# Main.net
KiCad netlist of a schematic drawn in Altium Designer
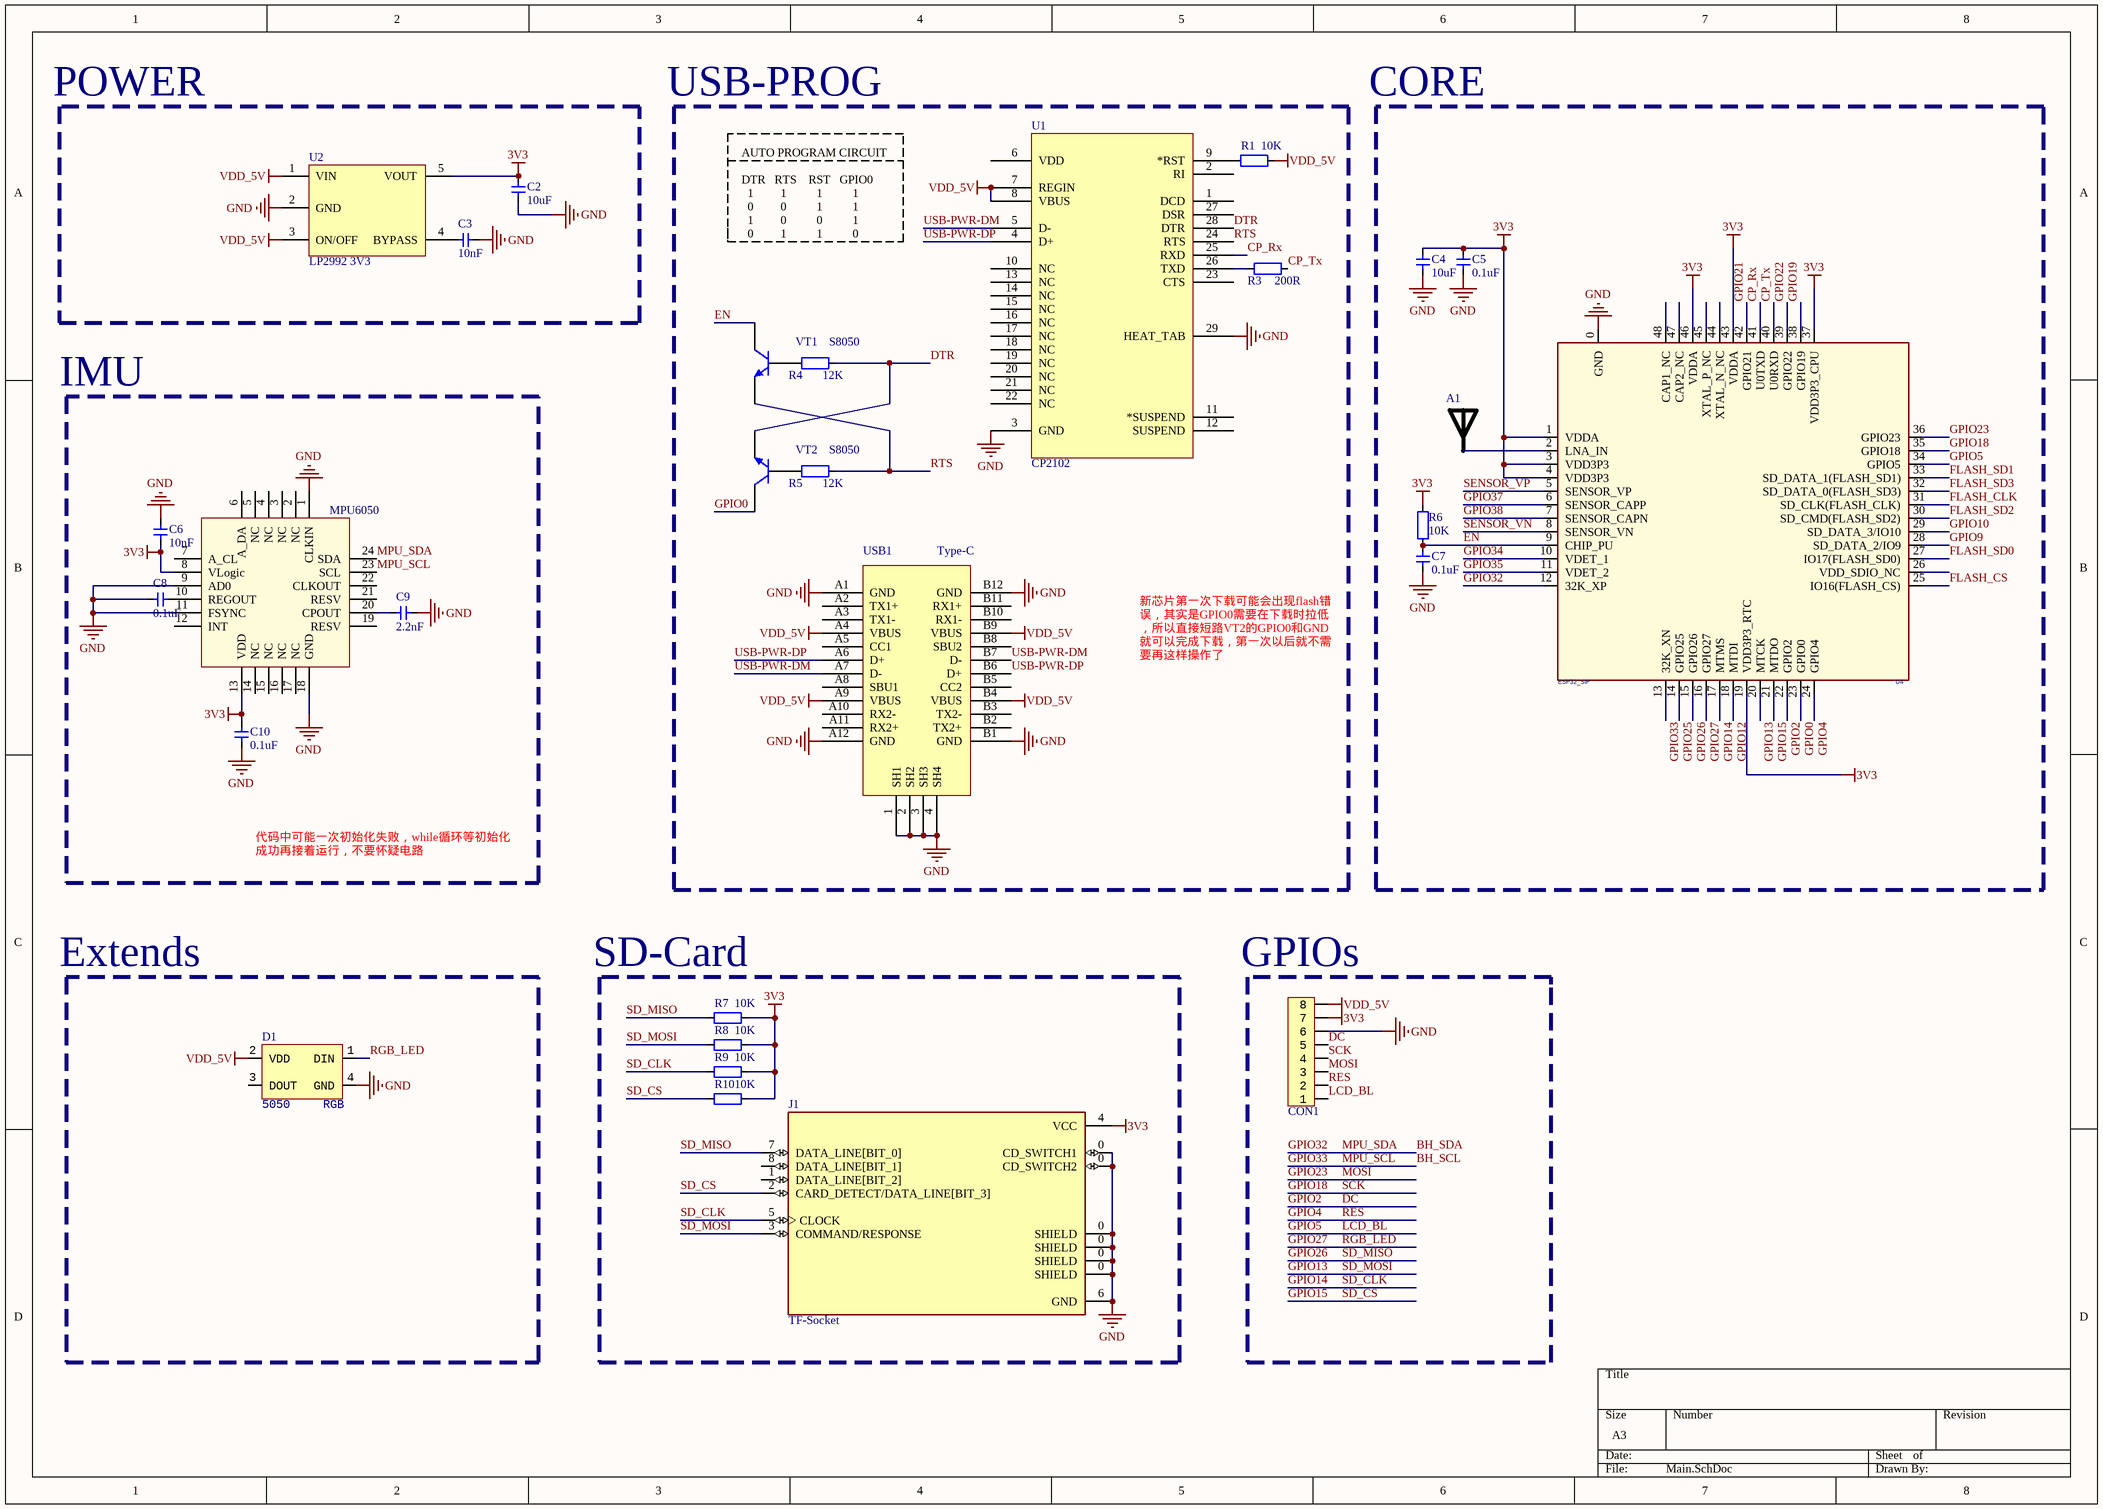
[diagram p0: Main.SchDoc]

(export (version "E")
  (design (tool "Eeschema 10.0.6"))
  (components
    (comp (ref "A1")
      (value "RAINSUN")
      (footprint "ANT-Rainsun-AN5120")
      (libsource (lib "MyPcbLib") (part "ANT-Rainsun-AP5120"))
    )
    (comp (ref "C2")
      (value "10uF")
      (footprint "CAP_0402")
      (description "Capacitor")
      (libsource (lib "MyPcbLib") (part "电容-0402"))
    )
    (comp (ref "C3")
      (value "10nF")
      (footprint "CAP_0402")
      (description "Capacitor")
      (libsource (lib "MyPcbLib") (part "电容-0402"))
    )
    (comp (ref "C4")
      (value "10uF")
      (footprint "CAP_0402")
      (description "Capacitor")
      (libsource (lib "MyPcbLib") (part "电容-0402"))
    )
    (comp (ref "C5")
      (value "0.1uF")
      (footprint "CAP_0402")
      (description "Capacitor")
      (libsource (lib "MyPcbLib") (part "电容-0402"))
    )
    (comp (ref "C6")
      (value "10nF")
      (footprint "CAP_0402")
      (description "Capacitor")
      (libsource (lib "MyPcbLib") (part "电容-0402"))
    )
    (comp (ref "C7")
      (value "0.1uF")
      (footprint "CAP_0402")
      (description "Capacitor")
      (libsource (lib "MyPcbLib") (part "电容-0402"))
    )
    (comp (ref "C8")
      (value "0.1uF")
      (footprint "CAP_0402")
      (description "Capacitor")
      (libsource (lib "MyPcbLib") (part "电容-0402"))
    )
    (comp (ref "C9")
      (value "2.2nF")
      (footprint "CAP_0402")
      (description "Capacitor")
      (libsource (lib "MyPcbLib") (part "电容-0402"))
    )
    (comp (ref "C10")
      (value "0.1uF")
      (footprint "CAP_0402")
      (description "Capacitor")
      (libsource (lib "MyPcbLib") (part "电容-0402"))
    )
    (comp (ref "CON1")
      (value "FFC_0.5_8")
      (footprint "FFC_0.5_8")
      (description "FFC")
      (libsource (lib "KitSprout") (part "FFC_0.5_8"))
    )
    (comp (ref "D1")
      (value "RGB")
      (footprint "LED_WS2812_CE")
      (description "LED")
      (fields (field (name "TYPE") "5050"))
      (libsource (lib "KitSprout") (part "LED_5050_WS2812B"))
    )
    (comp (ref "J1")
      (value "TF-Socket")
      (footprint "TF_F")
      (description "10 _8 + 2_ Position Card Connector Secure Digital - microSDâ„¢ Surface Mount, Right Angle Gold")
      (fields (field (name "MP") "1140084168") (field (name "MF") "Amphenol Commercial Products"))
      (libsource (lib "MyPcbLib") (part "TF-Socket"))
    )
    (comp (ref "R1")
      (value "10K")
      (footprint "RES_0402")
      (description "Resistor")
      (libsource (lib "MyPcbLib") (part "电阻-0402"))
    )
    (comp (ref "R3")
      (value "200R")
      (footprint "RES_0402")
      (description "Resistor")
      (libsource (lib "MyPcbLib") (part "电阻-0402"))
    )
    (comp (ref "R4")
      (value "12K")
      (footprint "RES_0402")
      (description "Resistor")
      (libsource (lib "MyPcbLib") (part "电阻-0402"))
    )
    (comp (ref "R5")
      (value "12K")
      (footprint "RES_0402")
      (description "Resistor")
      (libsource (lib "MyPcbLib") (part "电阻-0402"))
    )
    (comp (ref "R6")
      (value "10K")
      (footprint "RES_0402")
      (description "Resistor")
      (libsource (lib "") (part "电阻-0402_1"))
    )
    (comp (ref "R7")
      (value "10K")
      (footprint "RES_0402")
      (description "Resistor")
      (libsource (lib "MyPcbLib") (part "电阻-0402"))
    )
    (comp (ref "R8")
      (value "10K")
      (footprint "RES_0402")
      (description "Resistor")
      (libsource (lib "MyPcbLib") (part "电阻-0402"))
    )
    (comp (ref "R9")
      (value "10K")
      (footprint "RES_0402")
      (description "Resistor")
      (libsource (lib "MyPcbLib") (part "电阻-0402"))
    )
    (comp (ref "R10")
      (value "10K")
      (footprint "RES_0402")
      (description "Resistor")
      (libsource (lib "MyPcbLib") (part "电阻-0402"))
    )
    (comp (ref "U1")
      (value "CP2102")
      (footprint "QFN-28")
      (description "USB转TTL")
      (libsource (lib "mLib") (part "CP2102"))
    )
    (comp (ref "U2")
      (value "LP2992 3V3")
      (footprint "SOT23-5")
      (description "LDO")
      (libsource (lib "MyPcbLib") (part "LP2992"))
    )
    (comp (ref "U3")
      (value "MPU6050")
      (footprint "QFN-24")
      (description "六轴传感器")
      (libsource (lib "mLib") (part "MPU6050"))
    )
    (comp (ref "U4")
      (value "ESP32_SIP")
      (footprint "QFN-48_7X7")
      (libsource (lib "MyPcbLib") (part "ESP32-PICO"))
    )
    (comp (ref "USB1")
      (value "Type-C")
      (footprint "Type-C-TOP")
      (libsource (lib "MyPcbLib") (part "USB-Type-C-TOP"))
    )
    (comp (ref "VT1")
      (value "S8050")
      (footprint "SMT_TRIODE_NPN")
      (description "Surface mount NPN transistor, package SOT-23")
      (libsource (lib "MyPcbLib") (part "SMT_TRIODE_NPN"))
    )
    (comp (ref "VT2")
      (value "S8050")
      (footprint "SMT_TRIODE_NPN")
      (description "Surface mount NPN transistor, package SOT-23")
      (libsource (lib "MyPcbLib") (part "SMT_TRIODE_NPN"))
    )
  )
  (nets
    (net (code "1") (name "/BH_SCL") (class "Default")
      (node (ref "U3") (pin "23") (pinfunction "SCL_23") (pintype "passive"))
      (node (ref "U4") (pin "13") (pinfunction "32K_XN_13") (pintype "passive"))
    )
    (net (code "2") (name "/BH_SDA") (class "Default")
      (node (ref "U3") (pin "24") (pinfunction "SDA_24") (pintype "passive"))
      (node (ref "U4") (pin "12") (pinfunction "32K_XP_12") (pintype "passive"))
    )
    (net (code "3") (name "/CP_Rx") (class "Default")
      (node (ref "U1") (pin "25") (pinfunction "RXD_25") (pintype "passive"))
      (node (ref "U4") (pin "41") (pinfunction "U0TXD_41") (pintype "power_in"))
    )
    (net (code "4") (name "/CP_Tx") (class "Default")
      (node (ref "R3") (pin "1") (pinfunction "1_1") (pintype "passive"))
      (node (ref "U4") (pin "40") (pinfunction "U0RXD_40") (pintype "power_in"))
    )
    (net (code "5") (name "/DC") (class "Default")
      (node (ref "CON1") (pin "5") (pinfunction "5_5") (pintype "passive"))
      (node (ref "U4") (pin "22") (pinfunction "GPIO2_22") (pintype "passive"))
    )
    (net (code "6") (name "/DTR") (class "Default")
      (node (ref "R4") (pin "1") (pinfunction "1_1") (pintype "passive"))
      (node (ref "U1") (pin "28") (pinfunction "DTR_28") (pintype "passive"))
      (node (ref "VT2") (pin "2") (pinfunction "E_2") (pintype "passive"))
    )
    (net (code "7") (name "/EN") (class "Default")
      (node (ref "C7") (pin "1") (pinfunction "1_1") (pintype "passive"))
      (node (ref "R6") (pin "2") (pinfunction "2_2") (pintype "passive"))
      (node (ref "U4") (pin "9") (pinfunction "CHIP_PU_9") (pintype "passive"))
      (node (ref "VT1") (pin "3") (pinfunction "C_3") (pintype "passive"))
    )
    (net (code "8") (name "/FLASH_CLK") (class "Default")
      (node (ref "U4") (pin "31") (pinfunction "SD_CLK(FLASH_CLK)_31") (pintype "passive"))
    )
    (net (code "9") (name "/FLASH_CS") (class "Default")
      (node (ref "U4") (pin "25") (pinfunction "IO16(FLASH_CS)_25") (pintype "passive"))
    )
    (net (code "10") (name "/FLASH_SD0") (class "Default")
      (node (ref "U4") (pin "27") (pinfunction "IO17(FLASH_SD0)_27") (pintype "passive"))
    )
    (net (code "11") (name "/FLASH_SD1") (class "Default")
      (node (ref "U4") (pin "33") (pinfunction "SD_DATA_1(FLASH_SD1)_33") (pintype "passive"))
    )
    (net (code "12") (name "/FLASH_SD2") (class "Default")
      (node (ref "U4") (pin "30") (pinfunction "SD_CMD(FLASH_SD2)_30") (pintype "passive"))
    )
    (net (code "13") (name "/FLASH_SD3") (class "Default")
      (node (ref "U4") (pin "32") (pinfunction "SD_DATA_0(FLASH_SD3)_32") (pintype "passive"))
    )
    (net (code "14") (name "/GPIO0") (class "Default")
      (node (ref "U4") (pin "23") (pinfunction "GPIO0_23") (pintype "passive"))
      (node (ref "VT2") (pin "3") (pinfunction "C_3") (pintype "passive"))
    )
    (net (code "15") (name "/GPIO4") (class "Default")
      (node (ref "CON1") (pin "2") (pinfunction "2_2") (pintype "passive"))
      (node (ref "U4") (pin "24") (pinfunction "GPIO4_24") (pintype "passive"))
    )
    (net (code "16") (name "/GPIO5") (class "Default")
      (node (ref "CON1") (pin "1") (pinfunction "1_1") (pintype "passive"))
      (node (ref "U4") (pin "34") (pinfunction "GPIO5_34") (pintype "passive"))
    )
    (net (code "17") (name "/GPIO9") (class "Default")
      (node (ref "U4") (pin "28") (pinfunction "SD_DATA_2/IO9_28") (pintype "passive"))
    )
    (net (code "18") (name "/GPIO10") (class "Default")
      (node (ref "U4") (pin "29") (pinfunction "SD_DATA_3/IO10_29") (pintype "passive"))
    )
    (net (code "19") (name "/GPIO12") (class "Default")
      (node (ref "U4") (pin "18") (pinfunction "MTDI_18") (pintype "passive"))
    )
    (net (code "20") (name "/GPIO13") (class "Default")
      (node (ref "J1") (pin "3") (pinfunction "COMMAND/RESPONSE_3") (pintype "bidirectional"))
      (node (ref "R8") (pin "2") (pinfunction "2_2") (pintype "passive"))
      (node (ref "U4") (pin "20") (pinfunction "MTCK_20") (pintype "passive"))
    )
    (net (code "21") (name "/GPIO14") (class "Default")
      (node (ref "J1") (pin "5") (pinfunction "CLOCK_5") (pintype "bidirectional"))
      (node (ref "R9") (pin "2") (pinfunction "2_2") (pintype "passive"))
      (node (ref "U4") (pin "17") (pinfunction "MTMS_17") (pintype "passive"))
    )
    (net (code "22") (name "/GPIO15") (class "Default")
      (node (ref "J1") (pin "2") (pinfunction "CARD_DETECT/DATA_LINE[BIT_3]_2") (pintype "bidirectional"))
      (node (ref "R10") (pin "2") (pinfunction "2_2") (pintype "passive"))
      (node (ref "U4") (pin "21") (pinfunction "MTDO_21") (pintype "passive"))
    )
    (net (code "23") (name "/GPIO18") (class "Default")
      (node (ref "CON1") (pin "4") (pinfunction "4_4") (pintype "passive"))
      (node (ref "U4") (pin "35") (pinfunction "GPIO18_35") (pintype "passive"))
    )
    (net (code "24") (name "/GPIO19") (class "Default")
      (node (ref "U4") (pin "38") (pinfunction "GPIO19_38") (pintype "passive"))
    )
    (net (code "25") (name "/GPIO21") (class "Default")
      (node (ref "U4") (pin "42") (pinfunction "GPIO21_42") (pintype "passive"))
    )
    (net (code "26") (name "/GPIO22") (class "Default")
      (node (ref "U4") (pin "39") (pinfunction "GPIO22_39") (pintype "passive"))
    )
    (net (code "27") (name "/GPIO23") (class "Default")
      (node (ref "CON1") (pin "3") (pinfunction "3_3") (pintype "passive"))
      (node (ref "U4") (pin "36") (pinfunction "GPIO23_36") (pintype "passive"))
    )
    (net (code "28") (name "/GPIO25") (class "Default")
      (node (ref "U4") (pin "14") (pinfunction "GPIO25_14") (pintype "passive"))
    )
    (net (code "29") (name "/GPIO26") (class "Default")
      (node (ref "J1") (pin "7") (pinfunction "DATA_LINE[BIT_0]_7") (pintype "bidirectional"))
      (node (ref "R7") (pin "2") (pinfunction "2_2") (pintype "passive"))
      (node (ref "U4") (pin "15") (pinfunction "GPIO26_15") (pintype "passive"))
    )
    (net (code "30") (name "/GPIO27") (class "Default")
      (node (ref "D1") (pin "1") (pinfunction "DIN_1") (pintype "passive"))
      (node (ref "U4") (pin "16") (pinfunction "GPIO27_16") (pintype "passive"))
    )
    (net (code "31") (name "/GPIO34") (class "Default")
      (node (ref "U4") (pin "10") (pinfunction "VDET_1_10") (pintype "passive"))
    )
    (net (code "32") (name "/GPIO35") (class "Default")
      (node (ref "U4") (pin "11") (pinfunction "VDET_2_11") (pintype "passive"))
    )
    (net (code "33") (name "/GPIO37") (class "Default")
      (node (ref "U4") (pin "6") (pinfunction "SENSOR_CAPP_6") (pintype "passive"))
    )
    (net (code "34") (name "/GPIO38") (class "Default")
      (node (ref "U4") (pin "7") (pinfunction "SENSOR_CAPN_7") (pintype "passive"))
    )
    (net (code "35") (name "/RTS") (class "Default")
      (node (ref "R5") (pin "1") (pinfunction "1_1") (pintype "passive"))
      (node (ref "U1") (pin "24") (pinfunction "RTS_24") (pintype "passive"))
      (node (ref "VT1") (pin "2") (pinfunction "E_2") (pintype "passive"))
    )
    (net (code "36") (name "/SENSOR_VN") (class "Default")
      (node (ref "U4") (pin "8") (pinfunction "SENSOR_VN_8") (pintype "passive"))
    )
    (net (code "37") (name "/SENSOR_VP") (class "Default")
      (node (ref "U4") (pin "5") (pinfunction "SENSOR_VP_5") (pintype "passive"))
    )
    (net (code "38") (name "/USB-PWR-DM") (class "Default")
      (node (ref "U1") (pin "5") (pinfunction "D-_5") (pintype "passive"))
      (node (ref "USB1") (pin "A7") (pinfunction "D-_A7") (pintype "passive"))
      (node (ref "USB1") (pin "B7") (pinfunction "D-_B7") (pintype "passive"))
    )
    (net (code "39") (name "/USB-PWR-DP") (class "Default")
      (node (ref "U1") (pin "4") (pinfunction "D+_4") (pintype "passive"))
      (node (ref "USB1") (pin "A6") (pinfunction "D+_A6") (pintype "passive"))
      (node (ref "USB1") (pin "B6") (pinfunction "D+_B6") (pintype "passive"))
    )
    (net (code "40") (name "3V3") (class "Default")
      (node (ref "C10") (pin "2") (pinfunction "2_2") (pintype "passive"))
      (node (ref "C2") (pin "2") (pinfunction "2_2") (pintype "passive"))
      (node (ref "C4") (pin "2") (pinfunction "2_2") (pintype "passive"))
      (node (ref "C5") (pin "2") (pinfunction "2_2") (pintype "passive"))
      (node (ref "C6") (pin "1") (pinfunction "1_1") (pintype "passive"))
      (node (ref "CON1") (pin "7") (pinfunction "7_7") (pintype "passive"))
      (node (ref "J1") (pin "4") (pinfunction "VCC_4") (pintype "power_in"))
      (node (ref "R10") (pin "1") (pinfunction "1_1") (pintype "passive"))
      (node (ref "R6") (pin "1") (pinfunction "1_1") (pintype "passive"))
      (node (ref "R7") (pin "1") (pinfunction "1_1") (pintype "passive"))
      (node (ref "R8") (pin "1") (pinfunction "1_1") (pintype "passive"))
      (node (ref "R9") (pin "1") (pinfunction "1_1") (pintype "passive"))
      (node (ref "U2") (pin "5") (pinfunction "VOUT_5") (pintype "passive"))
      (node (ref "U3") (pin "13") (pinfunction "VDD_13") (pintype "passive"))
      (node (ref "U3") (pin "8") (pinfunction "VLogic_8") (pintype "passive"))
      (node (ref "U4") (pin "1") (pinfunction "VDDA_1") (pintype "power_in"))
      (node (ref "U4") (pin "19") (pinfunction "VDD3P3_RTC_19") (pintype "power_in"))
      (node (ref "U4") (pin "3") (pinfunction "VDD3P3_3") (pintype "power_in"))
      (node (ref "U4") (pin "37") (pinfunction "VDD3P3_CPU_37") (pintype "power_in"))
      (node (ref "U4") (pin "4") (pinfunction "VDD3P3_4") (pintype "power_in"))
      (node (ref "U4") (pin "43") (pinfunction "VDDA_43") (pintype "power_in"))
      (node (ref "U4") (pin "46") (pinfunction "VDDA_46") (pintype "power_in"))
    )
    (net (code "41") (name "GND") (class "Default")
      (node (ref "C10") (pin "1") (pinfunction "1_1") (pintype "passive"))
      (node (ref "C2") (pin "1") (pinfunction "1_1") (pintype "passive"))
      (node (ref "C3") (pin "1") (pinfunction "1_1") (pintype "passive"))
      (node (ref "C4") (pin "1") (pinfunction "1_1") (pintype "passive"))
      (node (ref "C5") (pin "1") (pinfunction "1_1") (pintype "passive"))
      (node (ref "C6") (pin "2") (pinfunction "2_2") (pintype "passive"))
      (node (ref "C7") (pin "2") (pinfunction "2_2") (pintype "passive"))
      (node (ref "C8") (pin "2") (pinfunction "2_2") (pintype "passive"))
      (node (ref "C9") (pin "1") (pinfunction "1_1") (pintype "passive"))
      (node (ref "CON1") (pin "6") (pinfunction "6_6") (pintype "passive"))
      (node (ref "D1") (pin "4") (pinfunction "GND_4") (pintype "passive"))
      (node (ref "J1") (pin "0") (pinfunction "SHIELD_0") (pintype "passive"))
      (node (ref "J1") (pin "6") (pinfunction "GND_6") (pintype "power_in"))
      (node (ref "U1") (pin "29") (pinfunction "HEAT_TAB_29") (pintype "passive"))
      (node (ref "U1") (pin "3") (pinfunction "GND_3") (pintype "passive"))
      (node (ref "U2") (pin "2") (pinfunction "GND_2") (pintype "passive"))
      (node (ref "U3") (pin "1") (pinfunction "CLKIN_1") (pintype "passive"))
      (node (ref "U3") (pin "11") (pinfunction "FSYNC_11") (pintype "passive"))
      (node (ref "U3") (pin "18") (pinfunction "GND_18") (pintype "passive"))
      (node (ref "U3") (pin "9") (pinfunction "AD0_9") (pintype "passive"))
      (node (ref "U4") (pin "0") (pinfunction "GND_0") (pintype "power_in"))
      (node (ref "USB1") (pin "1") (pinfunction "SH1_1") (pintype "passive"))
      (node (ref "USB1") (pin "2") (pinfunction "SH2_2") (pintype "passive"))
      (node (ref "USB1") (pin "3") (pinfunction "SH3_3") (pintype "passive"))
      (node (ref "USB1") (pin "4") (pinfunction "SH4_4") (pintype "passive"))
      (node (ref "USB1") (pin "A1") (pinfunction "GND_A1") (pintype "passive"))
      (node (ref "USB1") (pin "A12") (pinfunction "GND_A12") (pintype "passive"))
      (node (ref "USB1") (pin "B1") (pinfunction "GND_B1") (pintype "passive"))
      (node (ref "USB1") (pin "B12") (pinfunction "GND_B12") (pintype "passive"))
    )
    (net (code "42") (name "Net-(U1-*RST)") (class "Default")
      (node (ref "R1") (pin "2") (pinfunction "2_2") (pintype "passive"))
      (node (ref "U1") (pin "9") (pinfunction "*RST_9") (pintype "passive"))
    )
    (net (code "43") (name "Net-(U1-TXD)") (class "Default")
      (node (ref "R3") (pin "2") (pinfunction "2_2") (pintype "passive"))
      (node (ref "U1") (pin "26") (pinfunction "TXD_26") (pintype "passive"))
    )
    (net (code "44") (name "Net-(U2-BYPASS)") (class "Default")
      (node (ref "C3") (pin "2") (pinfunction "2_2") (pintype "passive"))
      (node (ref "U2") (pin "4") (pinfunction "BYPASS_4") (pintype "passive"))
    )
    (net (code "45") (name "Net-(U3-CPOUT)") (class "Default")
      (node (ref "C9") (pin "2") (pinfunction "2_2") (pintype "passive"))
      (node (ref "U3") (pin "20") (pinfunction "CPOUT_20") (pintype "passive"))
    )
    (net (code "46") (name "Net-(U3-REGOUT)") (class "Default")
      (node (ref "C8") (pin "1") (pinfunction "1_1") (pintype "passive"))
      (node (ref "U3") (pin "10") (pinfunction "REGOUT_10") (pintype "passive"))
    )
    (net (code "47") (name "Net-(U4-LNA_IN)") (class "Default")
      (node (ref "A1") (pin "1") (pinfunction "1_1") (pintype "passive"))
      (node (ref "U4") (pin "2") (pinfunction "LNA_IN_2") (pintype "passive"))
    )
    (net (code "48") (name "Net-(VT1-B)") (class "Default")
      (node (ref "R4") (pin "2") (pinfunction "2_2") (pintype "passive"))
      (node (ref "VT1") (pin "1") (pinfunction "B_1") (pintype "passive"))
    )
    (net (code "49") (name "Net-(VT2-B)") (class "Default")
      (node (ref "R5") (pin "2") (pinfunction "2_2") (pintype "passive"))
      (node (ref "VT2") (pin "1") (pinfunction "B_1") (pintype "passive"))
    )
    (net (code "50") (name "VDD_5V") (class "Default")
      (node (ref "CON1") (pin "8") (pinfunction "8_8") (pintype "passive"))
      (node (ref "D1") (pin "2") (pinfunction "VDD_2") (pintype "passive"))
      (node (ref "R1") (pin "1") (pinfunction "1_1") (pintype "passive"))
      (node (ref "U1") (pin "7") (pinfunction "REGIN_7") (pintype "passive"))
      (node (ref "U1") (pin "8") (pinfunction "VBUS_8") (pintype "passive"))
      (node (ref "U2") (pin "1") (pinfunction "VIN_1") (pintype "passive"))
      (node (ref "U2") (pin "3") (pinfunction "ON/OFF_3") (pintype "passive"))
      (node (ref "USB1") (pin "A4") (pinfunction "VBUS_A4") (pintype "passive"))
      (node (ref "USB1") (pin "A9") (pinfunction "VBUS_A9") (pintype "passive"))
      (node (ref "USB1") (pin "B4") (pinfunction "VBUS_B4") (pintype "passive"))
      (node (ref "USB1") (pin "B9") (pinfunction "VBUS_B9") (pintype "passive"))
    )
    (net (code "51") (name "unconnected-(D1-DOUT-Pad3)") (class "Default")
      (node (ref "D1") (pin "3") (pinfunction "DOUT_3") (pintype "passive"))
    )
    (net (code "52") (name "unconnected-(J1-DATA_LINE[BIT_1]-Pad8)") (class "Default")
      (node (ref "J1") (pin "8") (pinfunction "DATA_LINE[BIT_1]_8") (pintype "bidirectional"))
    )
    (net (code "53") (name "unconnected-(J1-DATA_LINE[BIT_2]-Pad1)") (class "Default")
      (node (ref "J1") (pin "1") (pinfunction "DATA_LINE[BIT_2]_1") (pintype "bidirectional"))
    )
    (net (code "54") (name "unconnected-(U1-*SUSPEND-Pad11)") (class "Default")
      (node (ref "U1") (pin "11") (pinfunction "*SUSPEND_11") (pintype "passive"))
    )
    (net (code "55") (name "unconnected-(U1-CTS-Pad23)") (class "Default")
      (node (ref "U1") (pin "23") (pinfunction "CTS_23") (pintype "passive"))
    )
    (net (code "56") (name "unconnected-(U1-DCD-Pad1)") (class "Default")
      (node (ref "U1") (pin "1") (pinfunction "DCD_1") (pintype "passive"))
    )
    (net (code "57") (name "unconnected-(U1-DSR-Pad27)") (class "Default")
      (node (ref "U1") (pin "27") (pinfunction "DSR_27") (pintype "passive"))
    )
    (net (code "58") (name "unconnected-(U1-NC-Pad10)") (class "Default")
      (node (ref "U1") (pin "10") (pinfunction "NC_10") (pintype "passive"))
    )
    (net (code "59") (name "unconnected-(U1-NC-Pad13)") (class "Default")
      (node (ref "U1") (pin "13") (pinfunction "NC_13") (pintype "passive"))
    )
    (net (code "60") (name "unconnected-(U1-NC-Pad14)") (class "Default")
      (node (ref "U1") (pin "14") (pinfunction "NC_14") (pintype "passive"))
    )
    (net (code "61") (name "unconnected-(U1-NC-Pad15)") (class "Default")
      (node (ref "U1") (pin "15") (pinfunction "NC_15") (pintype "passive"))
    )
    (net (code "62") (name "unconnected-(U1-NC-Pad16)") (class "Default")
      (node (ref "U1") (pin "16") (pinfunction "NC_16") (pintype "passive"))
    )
    (net (code "63") (name "unconnected-(U1-NC-Pad17)") (class "Default")
      (node (ref "U1") (pin "17") (pinfunction "NC_17") (pintype "passive"))
    )
    (net (code "64") (name "unconnected-(U1-NC-Pad18)") (class "Default")
      (node (ref "U1") (pin "18") (pinfunction "NC_18") (pintype "passive"))
    )
    (net (code "65") (name "unconnected-(U1-NC-Pad19)") (class "Default")
      (node (ref "U1") (pin "19") (pinfunction "NC_19") (pintype "passive"))
    )
    (net (code "66") (name "unconnected-(U1-NC-Pad20)") (class "Default")
      (node (ref "U1") (pin "20") (pinfunction "NC_20") (pintype "passive"))
    )
    (net (code "67") (name "unconnected-(U1-NC-Pad21)") (class "Default")
      (node (ref "U1") (pin "21") (pinfunction "NC_21") (pintype "passive"))
    )
    (net (code "68") (name "unconnected-(U1-NC-Pad22)") (class "Default")
      (node (ref "U1") (pin "22") (pinfunction "NC_22") (pintype "passive"))
    )
    (net (code "69") (name "unconnected-(U1-RI-Pad2)") (class "Default")
      (node (ref "U1") (pin "2") (pinfunction "RI_2") (pintype "passive"))
    )
    (net (code "70") (name "unconnected-(U1-SUSPEND-Pad12)") (class "Default")
      (node (ref "U1") (pin "12") (pinfunction "SUSPEND_12") (pintype "passive"))
    )
    (net (code "71") (name "unconnected-(U1-VDD-Pad6)") (class "Default")
      (node (ref "U1") (pin "6") (pinfunction "VDD_6") (pintype "passive"))
    )
    (net (code "72") (name "unconnected-(U3-A_CL-Pad7)") (class "Default")
      (node (ref "U3") (pin "7") (pinfunction "A_CL_7") (pintype "passive"))
    )
    (net (code "73") (name "unconnected-(U3-A_DA-Pad6)") (class "Default")
      (node (ref "U3") (pin "6") (pinfunction "A_DA_6") (pintype "passive"))
    )
    (net (code "74") (name "unconnected-(U3-CLKOUT-Pad22)") (class "Default")
      (node (ref "U3") (pin "22") (pinfunction "CLKOUT_22") (pintype "passive"))
    )
    (net (code "75") (name "unconnected-(U3-INT-Pad12)") (class "Default")
      (node (ref "U3") (pin "12") (pinfunction "INT_12") (pintype "passive"))
    )
    (net (code "76") (name "unconnected-(U3-NC-Pad2)") (class "Default")
      (node (ref "U3") (pin "2") (pinfunction "NC_2") (pintype "passive"))
    )
    (net (code "77") (name "unconnected-(U3-NC-Pad3)") (class "Default")
      (node (ref "U3") (pin "3") (pinfunction "NC_3") (pintype "passive"))
    )
    (net (code "78") (name "unconnected-(U3-NC-Pad4)") (class "Default")
      (node (ref "U3") (pin "4") (pinfunction "NC_4") (pintype "passive"))
    )
    (net (code "79") (name "unconnected-(U3-NC-Pad5)") (class "Default")
      (node (ref "U3") (pin "5") (pinfunction "NC_5") (pintype "passive"))
    )
    (net (code "80") (name "unconnected-(U3-NC-Pad14)") (class "Default")
      (node (ref "U3") (pin "14") (pinfunction "NC_14") (pintype "passive"))
    )
    (net (code "81") (name "unconnected-(U3-NC-Pad15)") (class "Default")
      (node (ref "U3") (pin "15") (pinfunction "NC_15") (pintype "passive"))
    )
    (net (code "82") (name "unconnected-(U3-NC-Pad16)") (class "Default")
      (node (ref "U3") (pin "16") (pinfunction "NC_16") (pintype "passive"))
    )
    (net (code "83") (name "unconnected-(U3-NC-Pad17)") (class "Default")
      (node (ref "U3") (pin "17") (pinfunction "NC_17") (pintype "passive"))
    )
    (net (code "84") (name "unconnected-(U3-RESV-Pad19)") (class "Default")
      (node (ref "U3") (pin "19") (pinfunction "RESV_19") (pintype "passive"))
    )
    (net (code "85") (name "unconnected-(U3-RESV-Pad21)") (class "Default")
      (node (ref "U3") (pin "21") (pinfunction "RESV_21") (pintype "passive"))
    )
    (net (code "86") (name "unconnected-(U4-CAP1_NC-Pad48)") (class "Default")
      (node (ref "U4") (pin "48") (pinfunction "CAP1_NC_48") (pintype "passive"))
    )
    (net (code "87") (name "unconnected-(U4-CAP2_NC-Pad47)") (class "Default")
      (node (ref "U4") (pin "47") (pinfunction "CAP2_NC_47") (pintype "passive"))
    )
    (net (code "88") (name "unconnected-(U4-VDD_SDIO_NC-Pad26)") (class "Default")
      (node (ref "U4") (pin "26") (pinfunction "VDD_SDIO_NC_26") (pintype "passive"))
    )
    (net (code "89") (name "unconnected-(U4-XTAL_N_NC-Pad44)") (class "Default")
      (node (ref "U4") (pin "44") (pinfunction "XTAL_N_NC_44") (pintype "passive"))
    )
    (net (code "90") (name "unconnected-(U4-XTAL_P_NC-Pad45)") (class "Default")
      (node (ref "U4") (pin "45") (pinfunction "XTAL_P_NC_45") (pintype "passive"))
    )
    (net (code "91") (name "unconnected-(USB1-CC1-PadA5)") (class "Default")
      (node (ref "USB1") (pin "A5") (pinfunction "CC1_A5") (pintype "passive"))
    )
    (net (code "92") (name "unconnected-(USB1-CC2-PadB5)") (class "Default")
      (node (ref "USB1") (pin "B5") (pinfunction "CC2_B5") (pintype "passive"))
    )
    (net (code "93") (name "unconnected-(USB1-RX1+-PadB11)") (class "Default")
      (node (ref "USB1") (pin "B11") (pinfunction "RX1+_B11") (pintype "passive"))
    )
    (net (code "94") (name "unconnected-(USB1-RX1--PadB10)") (class "Default")
      (node (ref "USB1") (pin "B10") (pinfunction "RX1-_B10") (pintype "passive"))
    )
    (net (code "95") (name "unconnected-(USB1-RX2+-PadA11)") (class "Default")
      (node (ref "USB1") (pin "A11") (pinfunction "RX2+_A11") (pintype "passive"))
    )
    (net (code "96") (name "unconnected-(USB1-RX2--PadA10)") (class "Default")
      (node (ref "USB1") (pin "A10") (pinfunction "RX2-_A10") (pintype "passive"))
    )
    (net (code "97") (name "unconnected-(USB1-SBU1-PadA8)") (class "Default")
      (node (ref "USB1") (pin "A8") (pinfunction "SBU1_A8") (pintype "passive"))
    )
    (net (code "98") (name "unconnected-(USB1-SBU2-PadB8)") (class "Default")
      (node (ref "USB1") (pin "B8") (pinfunction "SBU2_B8") (pintype "passive"))
    )
    (net (code "99") (name "unconnected-(USB1-TX1+-PadA2)") (class "Default")
      (node (ref "USB1") (pin "A2") (pinfunction "TX1+_A2") (pintype "passive"))
    )
    (net (code "100") (name "unconnected-(USB1-TX1--PadA3)") (class "Default")
      (node (ref "USB1") (pin "A3") (pinfunction "TX1-_A3") (pintype "passive"))
    )
    (net (code "101") (name "unconnected-(USB1-TX2+-PadB2)") (class "Default")
      (node (ref "USB1") (pin "B2") (pinfunction "TX2+_B2") (pintype "passive"))
    )
    (net (code "102") (name "unconnected-(USB1-TX2--PadB3)") (class "Default")
      (node (ref "USB1") (pin "B3") (pinfunction "TX2-_B3") (pintype "passive"))
    )
  )
)
